# RFID_antenna.net
KiCad netlist of a schematic drawn in EAGLE
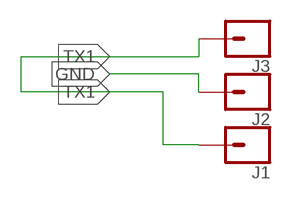
[diagram p0: schematic, sheet 1]

(export (version "E")
  (design (tool "Eeschema 10.0.6"))
  (components
    (comp (ref "J1")
      (value "CONN_01")
      (footprint "eagle-import:1X01")
      (libsource (lib "eagle-import") (part "CONN_01"))
    )
    (comp (ref "J2")
      (value "CONN_01")
      (footprint "eagle-import:1X01")
      (libsource (lib "eagle-import") (part "CONN_01"))
    )
    (comp (ref "J3")
      (value "CONN_01")
      (footprint "eagle-import:1X01")
      (libsource (lib "eagle-import") (part "CONN_01"))
    )
  )
  (nets
    (net (code "1") (name "GND") (class "Default")
      (node (ref "J2") (pin "1") (pinfunction "1_1") (pintype "passive"))
    )
    (net (code "2") (name "TX1") (class "Default")
      (node (ref "J1") (pin "1") (pinfunction "1_1") (pintype "passive"))
      (node (ref "J3") (pin "1") (pinfunction "1_1") (pintype "passive"))
    )
  )
)
